# untitled.net
KiCad netlist of a schematic drawn in EAGLE
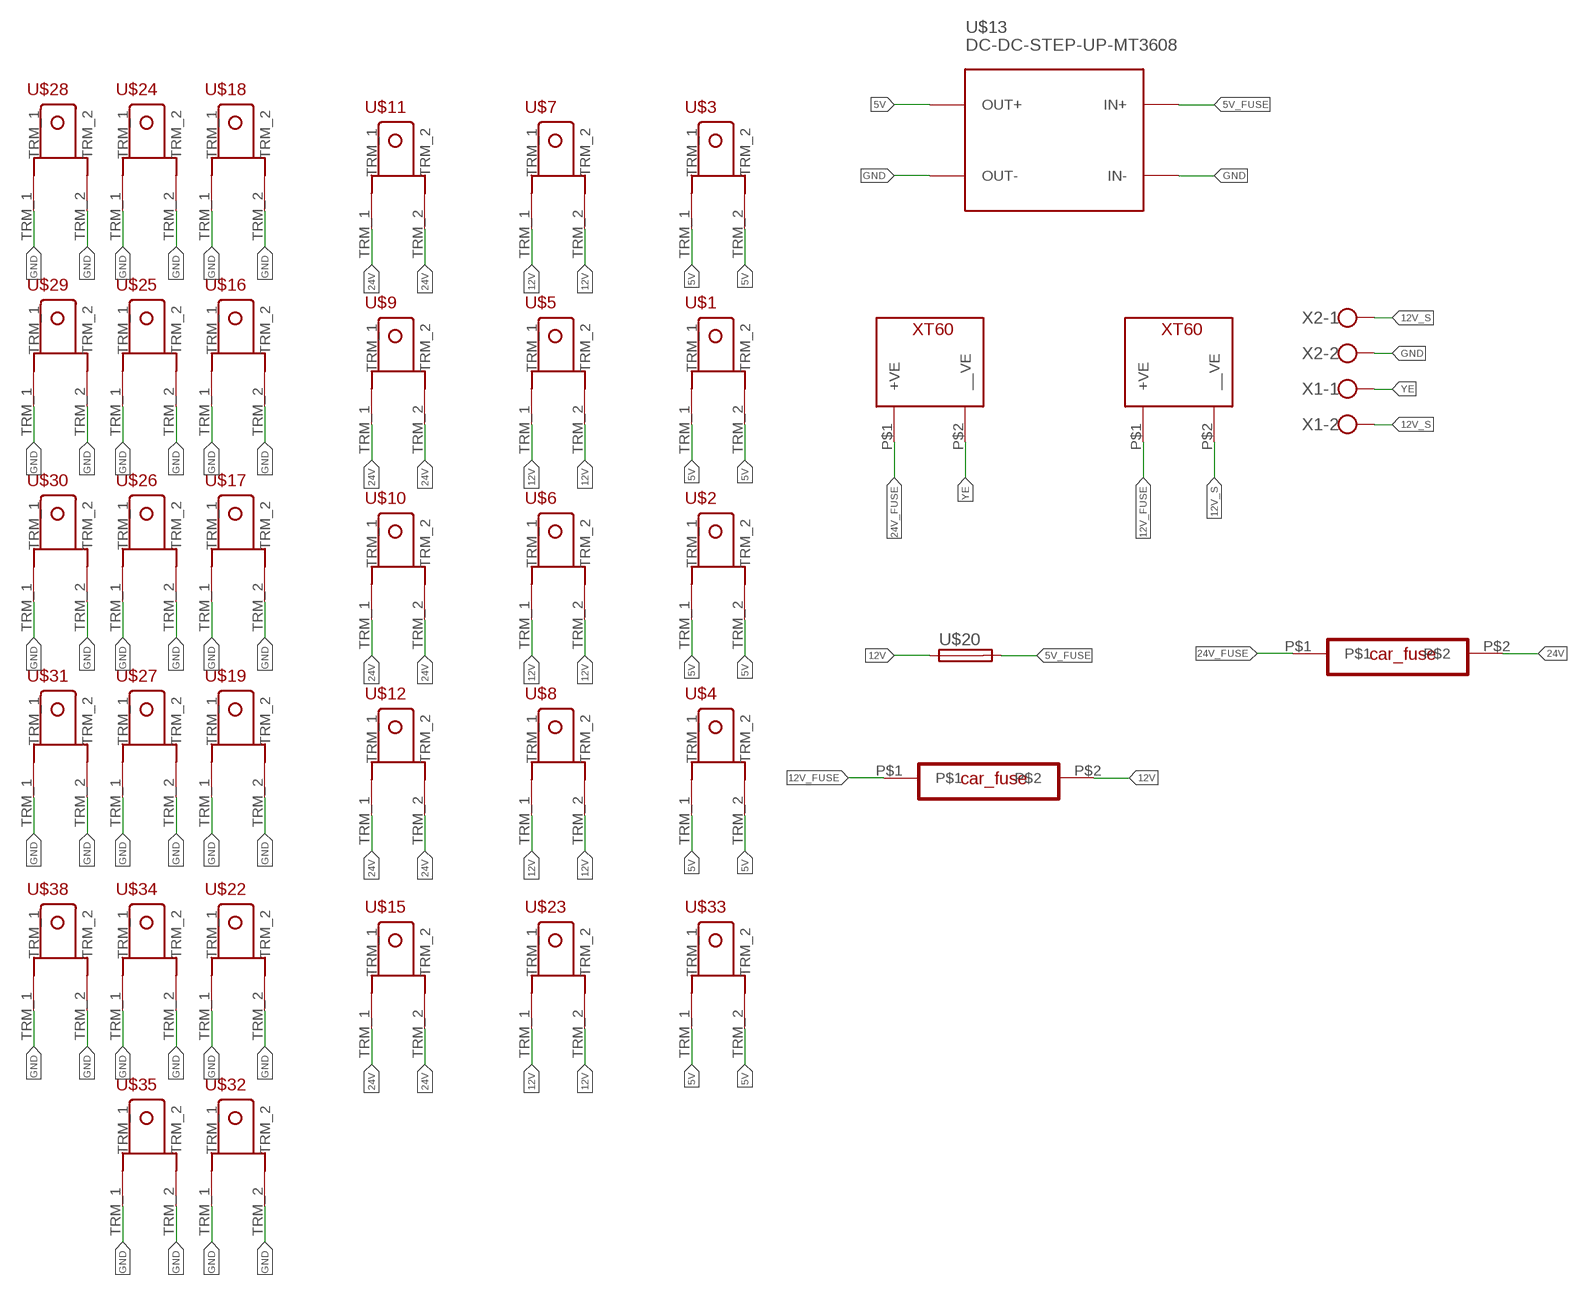
[diagram p0: schematic, sheet 1]

(export (version "E")
  (design (tool "Eeschema 10.0.6"))
  (components
    (comp (ref "U$1")
      (value "TERMINAL_EDITED")
      (footprint "eagle-import:TERMINAL_EDITED")
      (libsource (lib "eagle-import") (part "TERMINAL_EDITED"))
    )
    (comp (ref "U$2")
      (value "TERMINAL_EDITED")
      (footprint "eagle-import:TERMINAL_EDITED")
      (libsource (lib "eagle-import") (part "TERMINAL_EDITED"))
    )
    (comp (ref "U$3")
      (value "TERMINAL_EDITED")
      (footprint "eagle-import:TERMINAL_EDITED")
      (libsource (lib "eagle-import") (part "TERMINAL_EDITED"))
    )
    (comp (ref "U$4")
      (value "TERMINAL_EDITED")
      (footprint "eagle-import:TERMINAL_EDITED")
      (libsource (lib "eagle-import") (part "TERMINAL_EDITED"))
    )
    (comp (ref "U$5")
      (value "TERMINAL_EDITED")
      (footprint "eagle-import:TERMINAL_EDITED")
      (libsource (lib "eagle-import") (part "TERMINAL_EDITED"))
    )
    (comp (ref "U$6")
      (value "TERMINAL_EDITED")
      (footprint "eagle-import:TERMINAL_EDITED")
      (libsource (lib "eagle-import") (part "TERMINAL_EDITED"))
    )
    (comp (ref "U$7")
      (value "TERMINAL_EDITED")
      (footprint "eagle-import:TERMINAL_EDITED")
      (libsource (lib "eagle-import") (part "TERMINAL_EDITED"))
    )
    (comp (ref "U$8")
      (value "TERMINAL_EDITED")
      (footprint "eagle-import:TERMINAL_EDITED")
      (libsource (lib "eagle-import") (part "TERMINAL_EDITED"))
    )
    (comp (ref "U$9")
      (value "TERMINAL_EDITED")
      (footprint "eagle-import:TERMINAL_EDITED")
      (libsource (lib "eagle-import") (part "TERMINAL_EDITED"))
    )
    (comp (ref "U$10")
      (value "TERMINAL_EDITED")
      (footprint "eagle-import:TERMINAL_EDITED")
      (libsource (lib "eagle-import") (part "TERMINAL_EDITED"))
    )
    (comp (ref "U$11")
      (value "TERMINAL_EDITED")
      (footprint "eagle-import:TERMINAL_EDITED")
      (libsource (lib "eagle-import") (part "TERMINAL_EDITED"))
    )
    (comp (ref "U$12")
      (value "TERMINAL_EDITED")
      (footprint "eagle-import:TERMINAL_EDITED")
      (libsource (lib "eagle-import") (part "TERMINAL_EDITED"))
    )
    (comp (ref "U$13")
      (value "DC-DC-STEP-UP-MT3608")
      (footprint "eagle-import:DC-DC-STEP-UP-MT3608")
      (libsource (lib "eagle-import") (part "DC-DC-STEP-UP-MT3608"))
    )
    (comp (ref "U$14")
      (value "CAR_FUSE")
      (footprint "eagle-import:CAR_FUSE")
      (libsource (lib "eagle-import") (part "CAR_FUSE"))
    )
    (comp (ref "U$15")
      (value "TERMINAL_EDITED")
      (footprint "eagle-import:TERMINAL_EDITED")
      (libsource (lib "eagle-import") (part "TERMINAL_EDITED"))
    )
    (comp (ref "U$16")
      (value "TERMINAL_EDITED")
      (footprint "eagle-import:TERMINAL_EDITED")
      (libsource (lib "eagle-import") (part "TERMINAL_EDITED"))
    )
    (comp (ref "U$17")
      (value "TERMINAL_EDITED")
      (footprint "eagle-import:TERMINAL_EDITED")
      (libsource (lib "eagle-import") (part "TERMINAL_EDITED"))
    )
    (comp (ref "U$18")
      (value "TERMINAL_EDITED")
      (footprint "eagle-import:TERMINAL_EDITED")
      (libsource (lib "eagle-import") (part "TERMINAL_EDITED"))
    )
    (comp (ref "U$19")
      (value "TERMINAL_EDITED")
      (footprint "eagle-import:TERMINAL_EDITED")
      (libsource (lib "eagle-import") (part "TERMINAL_EDITED"))
    )
    (comp (ref "U$20")
      (value "FUSE_HOLDER")
      (footprint "eagle-import:SH22,5A")
      (libsource (lib "eagle-import") (part "FUSE_HOLDER"))
    )
    (comp (ref "U$21")
      (value "CAR_FUSE")
      (footprint "eagle-import:CAR_FUSE")
      (libsource (lib "eagle-import") (part "CAR_FUSE"))
    )
    (comp (ref "U$22")
      (value "TERMINAL_EDITED")
      (footprint "eagle-import:TERMINAL_EDITED")
      (libsource (lib "eagle-import") (part "TERMINAL_EDITED"))
    )
    (comp (ref "U$23")
      (value "TERMINAL_EDITED")
      (footprint "eagle-import:TERMINAL_EDITED")
      (libsource (lib "eagle-import") (part "TERMINAL_EDITED"))
    )
    (comp (ref "U$24")
      (value "TERMINAL_EDITED")
      (footprint "eagle-import:TERMINAL_EDITED")
      (libsource (lib "eagle-import") (part "TERMINAL_EDITED"))
    )
    (comp (ref "U$25")
      (value "TERMINAL_EDITED")
      (footprint "eagle-import:TERMINAL_EDITED")
      (libsource (lib "eagle-import") (part "TERMINAL_EDITED"))
    )
    (comp (ref "U$26")
      (value "TERMINAL_EDITED")
      (footprint "eagle-import:TERMINAL_EDITED")
      (libsource (lib "eagle-import") (part "TERMINAL_EDITED"))
    )
    (comp (ref "U$27")
      (value "TERMINAL_EDITED")
      (footprint "eagle-import:TERMINAL_EDITED")
      (libsource (lib "eagle-import") (part "TERMINAL_EDITED"))
    )
    (comp (ref "U$28")
      (value "TERMINAL_EDITED")
      (footprint "eagle-import:TERMINAL_EDITED")
      (libsource (lib "eagle-import") (part "TERMINAL_EDITED"))
    )
    (comp (ref "U$29")
      (value "TERMINAL_EDITED")
      (footprint "eagle-import:TERMINAL_EDITED")
      (libsource (lib "eagle-import") (part "TERMINAL_EDITED"))
    )
    (comp (ref "U$30")
      (value "TERMINAL_EDITED")
      (footprint "eagle-import:TERMINAL_EDITED")
      (libsource (lib "eagle-import") (part "TERMINAL_EDITED"))
    )
    (comp (ref "U$31")
      (value "TERMINAL_EDITED")
      (footprint "eagle-import:TERMINAL_EDITED")
      (libsource (lib "eagle-import") (part "TERMINAL_EDITED"))
    )
    (comp (ref "U$32")
      (value "TERMINAL_EDITED")
      (footprint "eagle-import:TERMINAL_EDITED")
      (libsource (lib "eagle-import") (part "TERMINAL_EDITED"))
    )
    (comp (ref "U$33")
      (value "TERMINAL_EDITED")
      (footprint "eagle-import:TERMINAL_EDITED")
      (libsource (lib "eagle-import") (part "TERMINAL_EDITED"))
    )
    (comp (ref "U$34")
      (value "TERMINAL_EDITED")
      (footprint "eagle-import:TERMINAL_EDITED")
      (libsource (lib "eagle-import") (part "TERMINAL_EDITED"))
    )
    (comp (ref "U$35")
      (value "TERMINAL_EDITED")
      (footprint "eagle-import:TERMINAL_EDITED")
      (libsource (lib "eagle-import") (part "TERMINAL_EDITED"))
    )
    (comp (ref "U$36")
      (value "XT60_CONNECTOR")
      (footprint "eagle-import:XT60")
      (libsource (lib "eagle-import") (part "XT60_CONNECTOR"))
    )
    (comp (ref "U$37")
      (value "XT60_CONNECTOR")
      (footprint "eagle-import:XT60")
      (libsource (lib "eagle-import") (part "XT60_CONNECTOR"))
    )
    (comp (ref "U$38")
      (value "TERMINAL_EDITED")
      (footprint "eagle-import:TERMINAL_EDITED")
      (libsource (lib "eagle-import") (part "TERMINAL_EDITED"))
    )
    (comp (ref "X1")
      (value "ROSTA.POWER")
      (footprint "eagle-import:W239-302")
      (libsource (lib "eagle-import") (part "ROSTA.POWER"))
    )
    (comp (ref "X2")
      (value "ROSTA.POWER")
      (footprint "eagle-import:W239-302")
      (libsource (lib "eagle-import") (part "ROSTA.POWER"))
    )
  )
  (nets
    (net (code "1") (name "5V") (class "Default")
      (node (ref "U$1") (pin "TRM_1") (pinfunction "TRM_1_TRM_1") (pintype "bidirectional"))
      (node (ref "U$1") (pin "TRM_2") (pinfunction "TRM_2_TRM_2") (pintype "bidirectional"))
      (node (ref "U$13") (pin "OUT+") (pinfunction "OUT+_OUT+") (pintype "bidirectional"))
      (node (ref "U$2") (pin "TRM_1") (pinfunction "TRM_1_TRM_1") (pintype "bidirectional"))
      (node (ref "U$2") (pin "TRM_2") (pinfunction "TRM_2_TRM_2") (pintype "bidirectional"))
      (node (ref "U$3") (pin "TRM_1") (pinfunction "TRM_1_TRM_1") (pintype "bidirectional"))
      (node (ref "U$3") (pin "TRM_2") (pinfunction "TRM_2_TRM_2") (pintype "bidirectional"))
      (node (ref "U$33") (pin "TRM_1") (pinfunction "TRM_1_TRM_1") (pintype "bidirectional"))
      (node (ref "U$33") (pin "TRM_2") (pinfunction "TRM_2_TRM_2") (pintype "bidirectional"))
      (node (ref "U$4") (pin "TRM_1") (pinfunction "TRM_1_TRM_1") (pintype "bidirectional"))
      (node (ref "U$4") (pin "TRM_2") (pinfunction "TRM_2_TRM_2") (pintype "bidirectional"))
    )
    (net (code "2") (name "5V_FUSE") (class "Default")
      (node (ref "U$13") (pin "IN+") (pinfunction "IN+_IN+") (pintype "bidirectional"))
      (node (ref "U$20") (pin "2") (pinfunction "2_2") (pintype "passive"))
    )
    (net (code "3") (name "12V") (class "Default")
      (node (ref "U$14") (pin "P$2") (pinfunction "P$2_P$2") (pintype "bidirectional"))
      (node (ref "U$20") (pin "1") (pinfunction "1_1") (pintype "passive"))
      (node (ref "U$23") (pin "TRM_1") (pinfunction "TRM_1_TRM_1") (pintype "bidirectional"))
      (node (ref "U$23") (pin "TRM_2") (pinfunction "TRM_2_TRM_2") (pintype "bidirectional"))
      (node (ref "U$5") (pin "TRM_1") (pinfunction "TRM_1_TRM_1") (pintype "bidirectional"))
      (node (ref "U$5") (pin "TRM_2") (pinfunction "TRM_2_TRM_2") (pintype "bidirectional"))
      (node (ref "U$6") (pin "TRM_1") (pinfunction "TRM_1_TRM_1") (pintype "bidirectional"))
      (node (ref "U$6") (pin "TRM_2") (pinfunction "TRM_2_TRM_2") (pintype "bidirectional"))
      (node (ref "U$7") (pin "TRM_1") (pinfunction "TRM_1_TRM_1") (pintype "bidirectional"))
      (node (ref "U$7") (pin "TRM_2") (pinfunction "TRM_2_TRM_2") (pintype "bidirectional"))
      (node (ref "U$8") (pin "TRM_1") (pinfunction "TRM_1_TRM_1") (pintype "bidirectional"))
      (node (ref "U$8") (pin "TRM_2") (pinfunction "TRM_2_TRM_2") (pintype "bidirectional"))
    )
    (net (code "4") (name "12V_FUSE") (class "Default")
      (node (ref "U$14") (pin "P$1") (pinfunction "P$1_P$1") (pintype "bidirectional"))
      (node (ref "U$37") (pin "P$1") (pinfunction "+VE_P$1") (pintype "bidirectional"))
    )
    (net (code "5") (name "12V_S") (class "Default")
      (node (ref "U$37") (pin "P$2") (pinfunction "__VE_P$2") (pintype "bidirectional"))
      (node (ref "X1") (pin "2") (pinfunction "KL_2") (pintype "passive"))
      (node (ref "X2") (pin "1") (pinfunction "KL_1") (pintype "passive"))
    )
    (net (code "6") (name "24V") (class "Default")
      (node (ref "U$10") (pin "TRM_1") (pinfunction "TRM_1_TRM_1") (pintype "bidirectional"))
      (node (ref "U$10") (pin "TRM_2") (pinfunction "TRM_2_TRM_2") (pintype "bidirectional"))
      (node (ref "U$11") (pin "TRM_1") (pinfunction "TRM_1_TRM_1") (pintype "bidirectional"))
      (node (ref "U$11") (pin "TRM_2") (pinfunction "TRM_2_TRM_2") (pintype "bidirectional"))
      (node (ref "U$12") (pin "TRM_1") (pinfunction "TRM_1_TRM_1") (pintype "bidirectional"))
      (node (ref "U$12") (pin "TRM_2") (pinfunction "TRM_2_TRM_2") (pintype "bidirectional"))
      (node (ref "U$15") (pin "TRM_1") (pinfunction "TRM_1_TRM_1") (pintype "bidirectional"))
      (node (ref "U$15") (pin "TRM_2") (pinfunction "TRM_2_TRM_2") (pintype "bidirectional"))
      (node (ref "U$21") (pin "P$2") (pinfunction "P$2_P$2") (pintype "bidirectional"))
      (node (ref "U$9") (pin "TRM_1") (pinfunction "TRM_1_TRM_1") (pintype "bidirectional"))
      (node (ref "U$9") (pin "TRM_2") (pinfunction "TRM_2_TRM_2") (pintype "bidirectional"))
    )
    (net (code "7") (name "24V_FUSE") (class "Default")
      (node (ref "U$21") (pin "P$1") (pinfunction "P$1_P$1") (pintype "bidirectional"))
      (node (ref "U$36") (pin "P$1") (pinfunction "+VE_P$1") (pintype "bidirectional"))
    )
    (net (code "8") (name "GND") (class "Default")
      (node (ref "U$13") (pin "IN-") (pinfunction "IN-_IN-") (pintype "bidirectional"))
      (node (ref "U$13") (pin "OUT-") (pinfunction "OUT-_OUT-") (pintype "bidirectional"))
      (node (ref "U$16") (pin "TRM_1") (pinfunction "TRM_1_TRM_1") (pintype "bidirectional"))
      (node (ref "U$16") (pin "TRM_2") (pinfunction "TRM_2_TRM_2") (pintype "bidirectional"))
      (node (ref "U$17") (pin "TRM_1") (pinfunction "TRM_1_TRM_1") (pintype "bidirectional"))
      (node (ref "U$17") (pin "TRM_2") (pinfunction "TRM_2_TRM_2") (pintype "bidirectional"))
      (node (ref "U$18") (pin "TRM_1") (pinfunction "TRM_1_TRM_1") (pintype "bidirectional"))
      (node (ref "U$18") (pin "TRM_2") (pinfunction "TRM_2_TRM_2") (pintype "bidirectional"))
      (node (ref "U$19") (pin "TRM_1") (pinfunction "TRM_1_TRM_1") (pintype "bidirectional"))
      (node (ref "U$19") (pin "TRM_2") (pinfunction "TRM_2_TRM_2") (pintype "bidirectional"))
      (node (ref "U$22") (pin "TRM_1") (pinfunction "TRM_1_TRM_1") (pintype "bidirectional"))
      (node (ref "U$22") (pin "TRM_2") (pinfunction "TRM_2_TRM_2") (pintype "bidirectional"))
      (node (ref "U$24") (pin "TRM_1") (pinfunction "TRM_1_TRM_1") (pintype "bidirectional"))
      (node (ref "U$24") (pin "TRM_2") (pinfunction "TRM_2_TRM_2") (pintype "bidirectional"))
      (node (ref "U$25") (pin "TRM_1") (pinfunction "TRM_1_TRM_1") (pintype "bidirectional"))
      (node (ref "U$25") (pin "TRM_2") (pinfunction "TRM_2_TRM_2") (pintype "bidirectional"))
      (node (ref "U$26") (pin "TRM_1") (pinfunction "TRM_1_TRM_1") (pintype "bidirectional"))
      (node (ref "U$26") (pin "TRM_2") (pinfunction "TRM_2_TRM_2") (pintype "bidirectional"))
      (node (ref "U$27") (pin "TRM_1") (pinfunction "TRM_1_TRM_1") (pintype "bidirectional"))
      (node (ref "U$27") (pin "TRM_2") (pinfunction "TRM_2_TRM_2") (pintype "bidirectional"))
      (node (ref "U$28") (pin "TRM_1") (pinfunction "TRM_1_TRM_1") (pintype "bidirectional"))
      (node (ref "U$28") (pin "TRM_2") (pinfunction "TRM_2_TRM_2") (pintype "bidirectional"))
      (node (ref "U$29") (pin "TRM_1") (pinfunction "TRM_1_TRM_1") (pintype "bidirectional"))
      (node (ref "U$29") (pin "TRM_2") (pinfunction "TRM_2_TRM_2") (pintype "bidirectional"))
      (node (ref "U$30") (pin "TRM_1") (pinfunction "TRM_1_TRM_1") (pintype "bidirectional"))
      (node (ref "U$30") (pin "TRM_2") (pinfunction "TRM_2_TRM_2") (pintype "bidirectional"))
      (node (ref "U$31") (pin "TRM_1") (pinfunction "TRM_1_TRM_1") (pintype "bidirectional"))
      (node (ref "U$31") (pin "TRM_2") (pinfunction "TRM_2_TRM_2") (pintype "bidirectional"))
      (node (ref "U$32") (pin "TRM_1") (pinfunction "TRM_1_TRM_1") (pintype "bidirectional"))
      (node (ref "U$32") (pin "TRM_2") (pinfunction "TRM_2_TRM_2") (pintype "bidirectional"))
      (node (ref "U$34") (pin "TRM_1") (pinfunction "TRM_1_TRM_1") (pintype "bidirectional"))
      (node (ref "U$34") (pin "TRM_2") (pinfunction "TRM_2_TRM_2") (pintype "bidirectional"))
      (node (ref "U$35") (pin "TRM_1") (pinfunction "TRM_1_TRM_1") (pintype "bidirectional"))
      (node (ref "U$35") (pin "TRM_2") (pinfunction "TRM_2_TRM_2") (pintype "bidirectional"))
      (node (ref "U$38") (pin "TRM_1") (pinfunction "TRM_1_TRM_1") (pintype "bidirectional"))
      (node (ref "U$38") (pin "TRM_2") (pinfunction "TRM_2_TRM_2") (pintype "bidirectional"))
      (node (ref "X2") (pin "2") (pinfunction "KL_2") (pintype "passive"))
    )
    (net (code "9") (name "YE") (class "Default")
      (node (ref "U$36") (pin "P$2") (pinfunction "__VE_P$2") (pintype "bidirectional"))
      (node (ref "X1") (pin "1") (pinfunction "KL_1") (pintype "passive"))
    )
  )
)
